# untitled.net
KiCad netlist of a schematic drawn in EAGLE
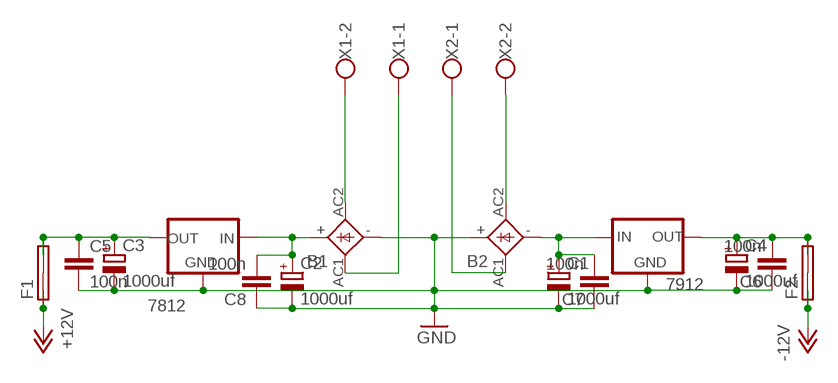
[diagram p0: schematic, sheet 1]
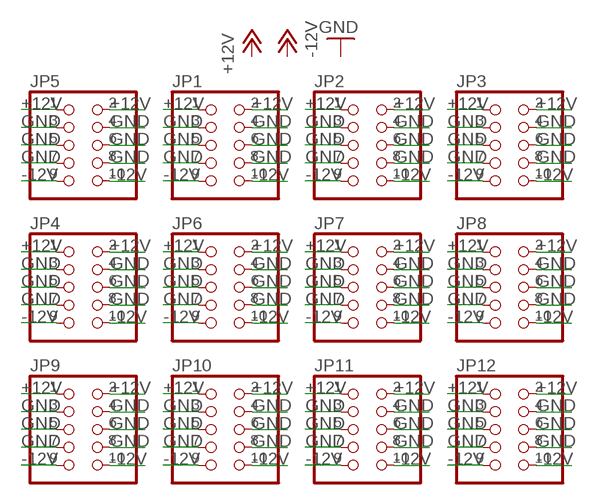
[diagram p1: schematic, sheet 2]

(export (version "E")
  (design (tool "Eeschema 10.0.6"))
  (components
    (comp (ref "7812")
      (value "79XXS")
      (footprint "eagle-import:79XXS")
      (libsource (lib "eagle-import") (part "79XXS"))
    )
    (comp (ref "7912")
      (value "78XXS")
      (footprint "eagle-import:78XXS")
      (libsource (lib "eagle-import") (part "78XXS"))
    )
    (comp (ref "B1")
      (value "FB15")
      (footprint "eagle-import:FB15")
      (libsource (lib "eagle-import") (part "FB15"))
    )
    (comp (ref "B2")
      (value "FB15")
      (footprint "eagle-import:FB15")
      (libsource (lib "eagle-import") (part "FB15"))
    )
    (comp (ref "C1")
      (value "1000uf")
      (footprint "eagle-import:TT5D11")
      (libsource (lib "eagle-import") (part "CPOL-EUTT5D11"))
    )
    (comp (ref "C2")
      (value "1000uf")
      (footprint "eagle-import:TT5D11")
      (libsource (lib "eagle-import") (part "CPOL-EUTT5D11"))
    )
    (comp (ref "C3")
      (value "1000uf")
      (footprint "eagle-import:TT5D11")
      (libsource (lib "eagle-import") (part "CPOL-EUTT5D11"))
    )
    (comp (ref "C4")
      (value "1000uf")
      (footprint "eagle-import:TT5D11")
      (libsource (lib "eagle-import") (part "CPOL-EUTT5D11"))
    )
    (comp (ref "C5")
      (value "100n")
      (footprint "eagle-import:C075-032X103")
      (libsource (lib "eagle-import") (part "C-EU075-032X103"))
    )
    (comp (ref "C6")
      (value "100n")
      (footprint "eagle-import:C075-032X103")
      (libsource (lib "eagle-import") (part "C-EU075-032X103"))
    )
    (comp (ref "C7")
      (value "100n")
      (footprint "eagle-import:C075-032X103")
      (libsource (lib "eagle-import") (part "C-EU075-032X103"))
    )
    (comp (ref "C8")
      (value "100n")
      (footprint "eagle-import:C075-032X103")
      (libsource (lib "eagle-import") (part "C-EU075-032X103"))
    )
    (comp (ref "F1")
      (value "SHK20L")
      (footprint "eagle-import:SHK20L")
      (libsource (lib "eagle-import") (part "SHK20L"))
    )
    (comp (ref "F2")
      (value "SHK20L")
      (footprint "eagle-import:SHK20L")
      (libsource (lib "eagle-import") (part "SHK20L"))
    )
    (comp (ref "X1")
      (value "W237-102")
      (footprint "eagle-import:W237-102")
      (fields (field (name "MPN") "237-102"))
      (libsource (lib "eagle-import") (part "W237-102"))
    )
    (comp (ref "X2")
      (value "W237-102")
      (footprint "eagle-import:W237-102")
      (fields (field (name "MPN") "237-102"))
      (libsource (lib "eagle-import") (part "W237-102"))
    )
    (comp (ref "JP1")
      (value "PINHD-2X5")
      (footprint "eagle-import:2X05")
      (libsource (lib "eagle-import") (part "PINHD-2X5"))
    )
    (comp (ref "JP2")
      (value "PINHD-2X5")
      (footprint "eagle-import:2X05")
      (libsource (lib "eagle-import") (part "PINHD-2X5"))
    )
    (comp (ref "JP3")
      (value "PINHD-2X5")
      (footprint "eagle-import:2X05")
      (libsource (lib "eagle-import") (part "PINHD-2X5"))
    )
    (comp (ref "JP4")
      (value "PINHD-2X5")
      (footprint "eagle-import:2X05")
      (libsource (lib "eagle-import") (part "PINHD-2X5"))
    )
    (comp (ref "JP5")
      (value "PINHD-2X5")
      (footprint "eagle-import:2X05")
      (libsource (lib "eagle-import") (part "PINHD-2X5"))
    )
    (comp (ref "JP6")
      (value "PINHD-2X5")
      (footprint "eagle-import:2X05")
      (libsource (lib "eagle-import") (part "PINHD-2X5"))
    )
    (comp (ref "JP7")
      (value "PINHD-2X5")
      (footprint "eagle-import:2X05")
      (libsource (lib "eagle-import") (part "PINHD-2X5"))
    )
    (comp (ref "JP8")
      (value "PINHD-2X5")
      (footprint "eagle-import:2X05")
      (libsource (lib "eagle-import") (part "PINHD-2X5"))
    )
    (comp (ref "JP9")
      (value "PINHD-2X5")
      (footprint "eagle-import:2X05")
      (libsource (lib "eagle-import") (part "PINHD-2X5"))
    )
    (comp (ref "JP10")
      (value "PINHD-2X5")
      (footprint "eagle-import:2X05")
      (libsource (lib "eagle-import") (part "PINHD-2X5"))
    )
    (comp (ref "JP11")
      (value "PINHD-2X5")
      (footprint "eagle-import:2X05")
      (libsource (lib "eagle-import") (part "PINHD-2X5"))
    )
    (comp (ref "JP12")
      (value "PINHD-2X5")
      (footprint "eagle-import:2X05")
      (libsource (lib "eagle-import") (part "PINHD-2X5"))
    )
  )
  (nets
    (net (code "1") (name "+12V") (class "Default")
      (node (ref "F1") (pin "1A") (pinfunction "1A_1A") (pintype "passive"))
      (node (ref "F1") (pin "1B") (pinfunction "1B_1B") (pintype "passive"))
      (node (ref "JP1") (pin "1") (pinfunction "1_1") (pintype "passive"))
      (node (ref "JP1") (pin "2") (pinfunction "2_2") (pintype "passive"))
      (node (ref "JP10") (pin "1") (pinfunction "1_1") (pintype "passive"))
      (node (ref "JP10") (pin "2") (pinfunction "2_2") (pintype "passive"))
      (node (ref "JP11") (pin "1") (pinfunction "1_1") (pintype "passive"))
      (node (ref "JP11") (pin "2") (pinfunction "2_2") (pintype "passive"))
      (node (ref "JP12") (pin "1") (pinfunction "1_1") (pintype "passive"))
      (node (ref "JP12") (pin "2") (pinfunction "2_2") (pintype "passive"))
      (node (ref "JP2") (pin "1") (pinfunction "1_1") (pintype "passive"))
      (node (ref "JP2") (pin "2") (pinfunction "2_2") (pintype "passive"))
      (node (ref "JP3") (pin "1") (pinfunction "1_1") (pintype "passive"))
      (node (ref "JP3") (pin "2") (pinfunction "2_2") (pintype "passive"))
      (node (ref "JP4") (pin "1") (pinfunction "1_1") (pintype "passive"))
      (node (ref "JP4") (pin "2") (pinfunction "2_2") (pintype "passive"))
      (node (ref "JP5") (pin "1") (pinfunction "1_1") (pintype "passive"))
      (node (ref "JP5") (pin "2") (pinfunction "2_2") (pintype "passive"))
      (node (ref "JP6") (pin "1") (pinfunction "1_1") (pintype "passive"))
      (node (ref "JP6") (pin "2") (pinfunction "2_2") (pintype "passive"))
      (node (ref "JP7") (pin "1") (pinfunction "1_1") (pintype "passive"))
      (node (ref "JP7") (pin "2") (pinfunction "2_2") (pintype "passive"))
      (node (ref "JP8") (pin "1") (pinfunction "1_1") (pintype "passive"))
      (node (ref "JP8") (pin "2") (pinfunction "2_2") (pintype "passive"))
      (node (ref "JP9") (pin "1") (pinfunction "1_1") (pintype "passive"))
      (node (ref "JP9") (pin "2") (pinfunction "2_2") (pintype "passive"))
    )
    (net (code "2") (name "-12V") (class "Default")
      (node (ref "F2") (pin "1A") (pinfunction "1A_1A") (pintype "passive"))
      (node (ref "F2") (pin "1B") (pinfunction "1B_1B") (pintype "passive"))
      (node (ref "JP1") (pin "10") (pinfunction "10_10") (pintype "passive"))
      (node (ref "JP1") (pin "9") (pinfunction "9_9") (pintype "passive"))
      (node (ref "JP10") (pin "10") (pinfunction "10_10") (pintype "passive"))
      (node (ref "JP10") (pin "9") (pinfunction "9_9") (pintype "passive"))
      (node (ref "JP11") (pin "10") (pinfunction "10_10") (pintype "passive"))
      (node (ref "JP11") (pin "9") (pinfunction "9_9") (pintype "passive"))
      (node (ref "JP12") (pin "10") (pinfunction "10_10") (pintype "passive"))
      (node (ref "JP12") (pin "9") (pinfunction "9_9") (pintype "passive"))
      (node (ref "JP2") (pin "10") (pinfunction "10_10") (pintype "passive"))
      (node (ref "JP2") (pin "9") (pinfunction "9_9") (pintype "passive"))
      (node (ref "JP3") (pin "10") (pinfunction "10_10") (pintype "passive"))
      (node (ref "JP3") (pin "9") (pinfunction "9_9") (pintype "passive"))
      (node (ref "JP4") (pin "10") (pinfunction "10_10") (pintype "passive"))
      (node (ref "JP4") (pin "9") (pinfunction "9_9") (pintype "passive"))
      (node (ref "JP5") (pin "10") (pinfunction "10_10") (pintype "passive"))
      (node (ref "JP5") (pin "9") (pinfunction "9_9") (pintype "passive"))
      (node (ref "JP6") (pin "10") (pinfunction "10_10") (pintype "passive"))
      (node (ref "JP6") (pin "9") (pinfunction "9_9") (pintype "passive"))
      (node (ref "JP7") (pin "10") (pinfunction "10_10") (pintype "passive"))
      (node (ref "JP7") (pin "9") (pinfunction "9_9") (pintype "passive"))
      (node (ref "JP8") (pin "10") (pinfunction "10_10") (pintype "passive"))
      (node (ref "JP8") (pin "9") (pinfunction "9_9") (pintype "passive"))
      (node (ref "JP9") (pin "10") (pinfunction "10_10") (pintype "passive"))
      (node (ref "JP9") (pin "9") (pinfunction "9_9") (pintype "passive"))
    )
    (net (code "3") (name "GND") (class "Default")
      (node (ref "7812") (pin "GND") (pinfunction "GND_GND") (pintype "input"))
      (node (ref "7912") (pin "GND") (pinfunction "GND_GND") (pintype "input"))
      (node (ref "B1") (pin "-") (pinfunction "-_-") (pintype "passive"))
      (node (ref "B2") (pin "+") (pinfunction "+_+") (pintype "passive"))
      (node (ref "C1") (pin "-") (pinfunction "-_-") (pintype "passive"))
      (node (ref "C2") (pin "-") (pinfunction "-_-") (pintype "passive"))
      (node (ref "C3") (pin "-") (pinfunction "-_-") (pintype "passive"))
      (node (ref "C4") (pin "-") (pinfunction "-_-") (pintype "passive"))
      (node (ref "C5") (pin "2") (pinfunction "2_2") (pintype "passive"))
      (node (ref "C6") (pin "1") (pinfunction "1_1") (pintype "passive"))
      (node (ref "C7") (pin "1") (pinfunction "1_1") (pintype "passive"))
      (node (ref "C8") (pin "1") (pinfunction "1_1") (pintype "passive"))
      (node (ref "JP1") (pin "3") (pinfunction "3_3") (pintype "passive"))
      (node (ref "JP1") (pin "4") (pinfunction "4_4") (pintype "passive"))
      (node (ref "JP1") (pin "5") (pinfunction "5_5") (pintype "passive"))
      (node (ref "JP1") (pin "6") (pinfunction "6_6") (pintype "passive"))
      (node (ref "JP1") (pin "7") (pinfunction "7_7") (pintype "passive"))
      (node (ref "JP1") (pin "8") (pinfunction "8_8") (pintype "passive"))
      (node (ref "JP10") (pin "3") (pinfunction "3_3") (pintype "passive"))
      (node (ref "JP10") (pin "4") (pinfunction "4_4") (pintype "passive"))
      (node (ref "JP10") (pin "5") (pinfunction "5_5") (pintype "passive"))
      (node (ref "JP10") (pin "6") (pinfunction "6_6") (pintype "passive"))
      (node (ref "JP10") (pin "7") (pinfunction "7_7") (pintype "passive"))
      (node (ref "JP10") (pin "8") (pinfunction "8_8") (pintype "passive"))
      (node (ref "JP11") (pin "3") (pinfunction "3_3") (pintype "passive"))
      (node (ref "JP11") (pin "4") (pinfunction "4_4") (pintype "passive"))
      (node (ref "JP11") (pin "5") (pinfunction "5_5") (pintype "passive"))
      (node (ref "JP11") (pin "6") (pinfunction "6_6") (pintype "passive"))
      (node (ref "JP11") (pin "7") (pinfunction "7_7") (pintype "passive"))
      (node (ref "JP11") (pin "8") (pinfunction "8_8") (pintype "passive"))
      (node (ref "JP12") (pin "3") (pinfunction "3_3") (pintype "passive"))
      (node (ref "JP12") (pin "4") (pinfunction "4_4") (pintype "passive"))
      (node (ref "JP12") (pin "5") (pinfunction "5_5") (pintype "passive"))
      (node (ref "JP12") (pin "6") (pinfunction "6_6") (pintype "passive"))
      (node (ref "JP12") (pin "7") (pinfunction "7_7") (pintype "passive"))
      (node (ref "JP12") (pin "8") (pinfunction "8_8") (pintype "passive"))
      (node (ref "JP2") (pin "3") (pinfunction "3_3") (pintype "passive"))
      (node (ref "JP2") (pin "4") (pinfunction "4_4") (pintype "passive"))
      (node (ref "JP2") (pin "5") (pinfunction "5_5") (pintype "passive"))
      (node (ref "JP2") (pin "6") (pinfunction "6_6") (pintype "passive"))
      (node (ref "JP2") (pin "7") (pinfunction "7_7") (pintype "passive"))
      (node (ref "JP2") (pin "8") (pinfunction "8_8") (pintype "passive"))
      (node (ref "JP3") (pin "3") (pinfunction "3_3") (pintype "passive"))
      (node (ref "JP3") (pin "4") (pinfunction "4_4") (pintype "passive"))
      (node (ref "JP3") (pin "5") (pinfunction "5_5") (pintype "passive"))
      (node (ref "JP3") (pin "6") (pinfunction "6_6") (pintype "passive"))
      (node (ref "JP3") (pin "7") (pinfunction "7_7") (pintype "passive"))
      (node (ref "JP3") (pin "8") (pinfunction "8_8") (pintype "passive"))
      (node (ref "JP4") (pin "3") (pinfunction "3_3") (pintype "passive"))
      (node (ref "JP4") (pin "4") (pinfunction "4_4") (pintype "passive"))
      (node (ref "JP4") (pin "5") (pinfunction "5_5") (pintype "passive"))
      (node (ref "JP4") (pin "6") (pinfunction "6_6") (pintype "passive"))
      (node (ref "JP4") (pin "7") (pinfunction "7_7") (pintype "passive"))
      (node (ref "JP4") (pin "8") (pinfunction "8_8") (pintype "passive"))
      (node (ref "JP5") (pin "3") (pinfunction "3_3") (pintype "passive"))
      (node (ref "JP5") (pin "4") (pinfunction "4_4") (pintype "passive"))
      (node (ref "JP5") (pin "5") (pinfunction "5_5") (pintype "passive"))
      (node (ref "JP5") (pin "6") (pinfunction "6_6") (pintype "passive"))
      (node (ref "JP5") (pin "7") (pinfunction "7_7") (pintype "passive"))
      (node (ref "JP5") (pin "8") (pinfunction "8_8") (pintype "passive"))
      (node (ref "JP6") (pin "3") (pinfunction "3_3") (pintype "passive"))
      (node (ref "JP6") (pin "4") (pinfunction "4_4") (pintype "passive"))
      (node (ref "JP6") (pin "5") (pinfunction "5_5") (pintype "passive"))
      (node (ref "JP6") (pin "6") (pinfunction "6_6") (pintype "passive"))
      (node (ref "JP6") (pin "7") (pinfunction "7_7") (pintype "passive"))
      (node (ref "JP6") (pin "8") (pinfunction "8_8") (pintype "passive"))
      (node (ref "JP7") (pin "3") (pinfunction "3_3") (pintype "passive"))
      (node (ref "JP7") (pin "4") (pinfunction "4_4") (pintype "passive"))
      (node (ref "JP7") (pin "5") (pinfunction "5_5") (pintype "passive"))
      (node (ref "JP7") (pin "6") (pinfunction "6_6") (pintype "passive"))
      (node (ref "JP7") (pin "7") (pinfunction "7_7") (pintype "passive"))
      (node (ref "JP7") (pin "8") (pinfunction "8_8") (pintype "passive"))
      (node (ref "JP8") (pin "3") (pinfunction "3_3") (pintype "passive"))
      (node (ref "JP8") (pin "4") (pinfunction "4_4") (pintype "passive"))
      (node (ref "JP8") (pin "5") (pinfunction "5_5") (pintype "passive"))
      (node (ref "JP8") (pin "6") (pinfunction "6_6") (pintype "passive"))
      (node (ref "JP8") (pin "7") (pinfunction "7_7") (pintype "passive"))
      (node (ref "JP8") (pin "8") (pinfunction "8_8") (pintype "passive"))
      (node (ref "JP9") (pin "3") (pinfunction "3_3") (pintype "passive"))
      (node (ref "JP9") (pin "4") (pinfunction "4_4") (pintype "passive"))
      (node (ref "JP9") (pin "5") (pinfunction "5_5") (pintype "passive"))
      (node (ref "JP9") (pin "6") (pinfunction "6_6") (pintype "passive"))
      (node (ref "JP9") (pin "7") (pinfunction "7_7") (pintype "passive"))
      (node (ref "JP9") (pin "8") (pinfunction "8_8") (pintype "passive"))
    )
    (net (code "4") (name "Net-(7812-PadIN)") (class "Default")
      (node (ref "7812") (pin "IN") (pinfunction "IN_IN") (pintype "input"))
      (node (ref "B1") (pin "+") (pinfunction "+_+") (pintype "passive"))
      (node (ref "C2") (pin "+") (pinfunction "+_+") (pintype "passive"))
      (node (ref "C8") (pin "2") (pinfunction "2_2") (pintype "passive"))
    )
    (net (code "5") (name "Net-(7812-PadOUT)") (class "Default")
      (node (ref "7812") (pin "OUT") (pinfunction "OUT_OUT") (pintype "passive"))
      (node (ref "C3") (pin "+") (pinfunction "+_+") (pintype "passive"))
      (node (ref "C5") (pin "1") (pinfunction "1_1") (pintype "passive"))
      (node (ref "F1") (pin "2A") (pinfunction "2A_2A") (pintype "passive"))
      (node (ref "F1") (pin "2B") (pinfunction "2B_2B") (pintype "passive"))
    )
    (net (code "6") (name "Net-(7912-PadIN)") (class "Default")
      (node (ref "7912") (pin "IN") (pinfunction "IN_IN") (pintype "input"))
      (node (ref "B2") (pin "-") (pinfunction "-_-") (pintype "passive"))
      (node (ref "C1") (pin "+") (pinfunction "+_+") (pintype "passive"))
      (node (ref "C7") (pin "2") (pinfunction "2_2") (pintype "passive"))
    )
    (net (code "7") (name "Net-(7912-PadOUT)") (class "Default")
      (node (ref "7912") (pin "OUT") (pinfunction "OUT_OUT") (pintype "passive"))
      (node (ref "C4") (pin "+") (pinfunction "+_+") (pintype "passive"))
      (node (ref "C6") (pin "2") (pinfunction "2_2") (pintype "passive"))
      (node (ref "F2") (pin "2A") (pinfunction "2A_2A") (pintype "passive"))
      (node (ref "F2") (pin "2B") (pinfunction "2B_2B") (pintype "passive"))
    )
    (net (code "8") (name "Net-(X1A-KL)") (class "Default")
      (node (ref "B1") (pin "AC1") (pinfunction "AC1_AC1") (pintype "passive"))
      (node (ref "X1") (pin "1") (pinfunction "KL_1") (pintype "passive"))
    )
    (net (code "9") (name "Net-(X1B-KL)") (class "Default")
      (node (ref "B1") (pin "AC2") (pinfunction "AC2_AC2") (pintype "passive"))
      (node (ref "X1") (pin "2") (pinfunction "KL_2") (pintype "passive"))
    )
    (net (code "10") (name "Net-(X2A-KL)") (class "Default")
      (node (ref "B2") (pin "AC1") (pinfunction "AC1_AC1") (pintype "passive"))
      (node (ref "X2") (pin "1") (pinfunction "KL_1") (pintype "passive"))
    )
    (net (code "11") (name "Net-(X2B-KL)") (class "Default")
      (node (ref "B2") (pin "AC2") (pinfunction "AC2_AC2") (pintype "passive"))
      (node (ref "X2") (pin "2") (pinfunction "KL_2") (pintype "passive"))
    )
  )
)
